# EtnaNode1_0.net
KiCad netlist of a schematic drawn in EAGLE
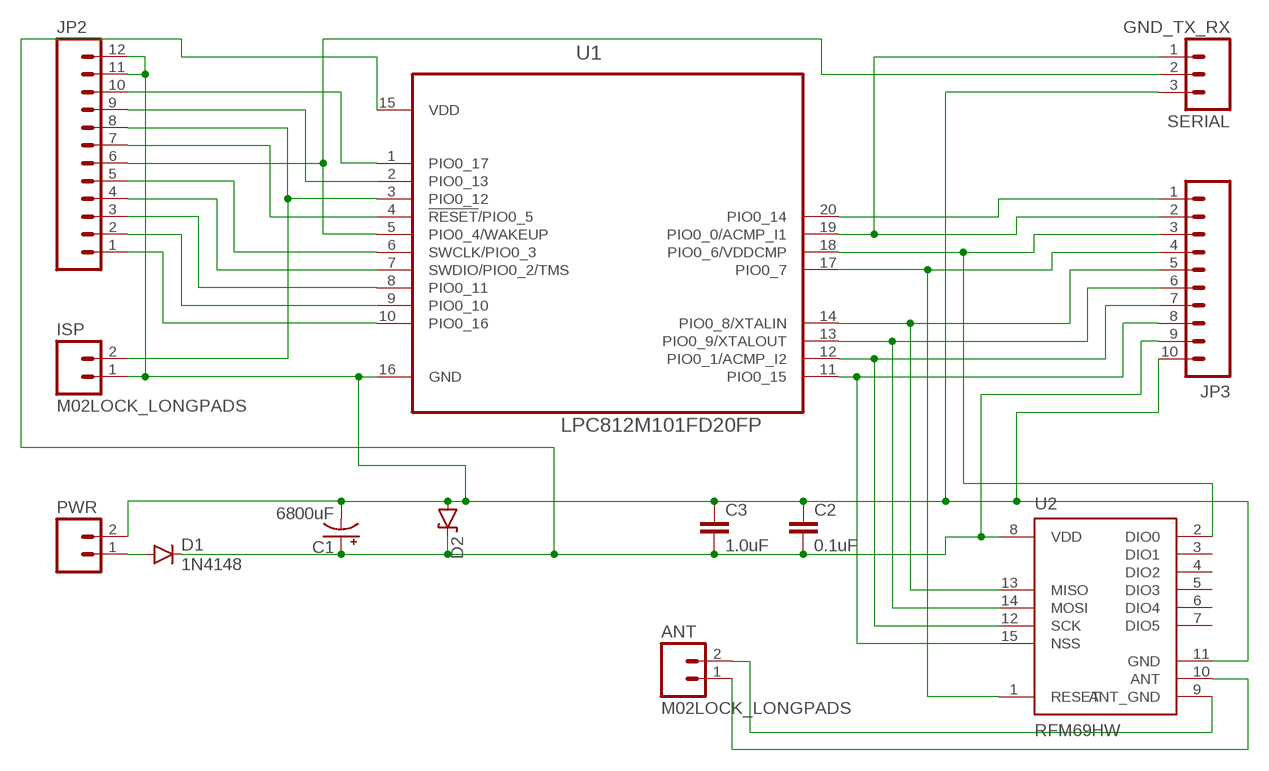
[diagram p0: schematic, sheet 1]

(export (version "E")
  (design (tool "Eeschema 10.0.6"))
  (components
    (comp (ref "ANT")
      (value "M02LOCK_LONGPADS")
      (footprint "eagle-import:1X02_LOCK_LONGPADS")
      (libsource (lib "eagle-import") (part "M02LOCK_LONGPADS"))
    )
    (comp (ref "C1")
      (value "6800uF")
      (footprint "eagle-import:CPOL-RADIAL-1000UF-25V")
      (libsource (lib "eagle-import") (part "CAP_POLPTH4"))
    )
    (comp (ref "C2")
      (value "0.1uF")
      (footprint "eagle-import:CAP-PTH-SMALL")
      (libsource (lib "eagle-import") (part "CAPPTH"))
    )
    (comp (ref "C3")
      (value "1.0uF")
      (footprint "eagle-import:CAP-PTH-SMALL")
      (libsource (lib "eagle-import") (part "CAPPTH"))
    )
    (comp (ref "D1")
      (value "1N4148")
      (footprint "eagle-import:DIODE-1N4148")
      (libsource (lib "eagle-import") (part "DIODE1N4148"))
    )
    (comp (ref "D2")
      (value "DIODE-ZENERPTH")
      (footprint "eagle-import:DIODE-ZENER")
      (libsource (lib "eagle-import") (part "DIODE-ZENERPTH"))
    )
    (comp (ref "ISP")
      (value "M02LOCK_LONGPADS")
      (footprint "eagle-import:1X02_LOCK_LONGPADS")
      (libsource (lib "eagle-import") (part "M02LOCK_LONGPADS"))
    )
    (comp (ref "JP2")
      (value "M12LOCK_LONGPADS")
      (footprint "eagle-import:1X12_LOCK_LONGPADS")
      (libsource (lib "eagle-import") (part "M12LOCK_LONGPADS"))
    )
    (comp (ref "JP3")
      (value "M10LOCK_LONGPADS")
      (footprint "eagle-import:1X10_LOCK_LONGPADS")
      (libsource (lib "eagle-import") (part "M10LOCK_LONGPADS"))
    )
    (comp (ref "PWR")
      (value "M02LOCK_LONGPADS")
      (footprint "eagle-import:1X02_LOCK_LONGPADS")
      (libsource (lib "eagle-import") (part "M02LOCK_LONGPADS"))
    )
    (comp (ref "SERIAL")
      (value "GND_TX_RX")
      (footprint "eagle-import:1X03_LOCK_LONGPADS")
      (libsource (lib "eagle-import") (part "M03LOCK_LONGPADS"))
    )
    (comp (ref "U1")
      (value "LPC812M101FD20FP")
      (footprint "eagle-import:SOIC127P1032X265-20N")
      (libsource (lib "eagle-import") (part "LPC812M101FD20FP"))
    )
    (comp (ref "U2")
      (value "RFM69HW")
      (footprint "eagle-import:RFM69W-XXXS2")
      (libsource (lib "eagle-import") (part "RFM69HW"))
    )
  )
  (nets
    (net (code "1") (name "Net-(D1-PadA)") (class "Default")
      (node (ref "D1") (pin "A") (pinfunction "A_A") (pintype "passive"))
      (node (ref "PWR") (pin "1") (pinfunction "1_1") (pintype "passive"))
    )
    (net (code "2") (name "Net-(D2-A)") (class "Default")
      (node (ref "C1") (pin "-") (pinfunction "-_-") (pintype "passive"))
      (node (ref "C2") (pin "1") (pinfunction "1_1") (pintype "passive"))
      (node (ref "C3") (pin "1") (pinfunction "1_1") (pintype "passive"))
      (node (ref "D2") (pin "P$2") (pinfunction "A_P$2") (pintype "passive"))
      (node (ref "ISP") (pin "1") (pinfunction "1_1") (pintype "passive"))
      (node (ref "JP2") (pin "11") (pinfunction "11_11") (pintype "passive"))
      (node (ref "JP2") (pin "12") (pinfunction "VCC_12") (pintype "passive"))
      (node (ref "JP3") (pin "10") (pinfunction "10_10") (pintype "passive"))
      (node (ref "PWR") (pin "2") (pinfunction "2_2") (pintype "passive"))
      (node (ref "SERIAL") (pin "3") (pinfunction "U0_RXD_3") (pintype "passive"))
      (node (ref "U1") (pin "16") (pinfunction "GND_16") (pintype "power_in"))
      (node (ref "U2") (pin "11") (pinfunction "GND_11") (pintype "power_in"))
    )
    (net (code "3") (name "Net-(D2-C)") (class "Default")
      (node (ref "C1") (pin "+") (pinfunction "+_+") (pintype "passive"))
      (node (ref "C2") (pin "2") (pinfunction "2_2") (pintype "passive"))
      (node (ref "C3") (pin "2") (pinfunction "2_2") (pintype "passive"))
      (node (ref "D1") (pin "C") (pinfunction "C_C") (pintype "passive"))
      (node (ref "D2") (pin "P$1") (pinfunction "C_P$1") (pintype "passive"))
      (node (ref "JP3") (pin "9") (pinfunction "9_9") (pintype "passive"))
      (node (ref "U1") (pin "15") (pinfunction "VDD_15") (pintype "power_in"))
      (node (ref "U2") (pin "8") (pinfunction "VDD_8") (pintype "power_in"))
    )
    (net (code "4") (name "Net-(SERIAL-GND)") (class "Default")
      (node (ref "JP3") (pin "2") (pinfunction "2_2") (pintype "passive"))
      (node (ref "SERIAL") (pin "1") (pinfunction "GND_1") (pintype "passive"))
      (node (ref "U1") (pin "19") (pinfunction "PIO0_0/ACMP_I1_19") (pintype "bidirectional"))
    )
    (net (code "5") (name "Net-(SERIAL-U0_TXD)") (class "Default")
      (node (ref "JP2") (pin "6") (pinfunction "6_6") (pintype "passive"))
      (node (ref "SERIAL") (pin "2") (pinfunction "U0_TXD_2") (pintype "passive"))
      (node (ref "U1") (pin "5") (pinfunction "PIO0_4/WAKEUP_5") (pintype "bidirectional"))
    )
    (net (code "6") (name "Net-(U1-PIO0_1{slash}ACMP_I2)") (class "Default")
      (node (ref "JP3") (pin "7") (pinfunction "7_7") (pintype "passive"))
      (node (ref "U1") (pin "12") (pinfunction "PIO0_1/ACMP_I2_12") (pintype "bidirectional"))
      (node (ref "U2") (pin "12") (pinfunction "SCK_12") (pintype "input"))
    )
    (net (code "7") (name "Net-(U1-PIO0_6{slash}VDDCMP)") (class "Default")
      (node (ref "JP3") (pin "3") (pinfunction "3_3") (pintype "passive"))
      (node (ref "U1") (pin "18") (pinfunction "PIO0_6/VDDCMP_18") (pintype "bidirectional"))
      (node (ref "U2") (pin "2") (pinfunction "DIO0_2") (pintype "bidirectional"))
    )
    (net (code "8") (name "Net-(U1-PIO0_7)") (class "Default")
      (node (ref "JP3") (pin "4") (pinfunction "4_4") (pintype "passive"))
      (node (ref "U1") (pin "17") (pinfunction "PIO0_7_17") (pintype "bidirectional"))
      (node (ref "U2") (pin "1") (pinfunction "RESET_1") (pintype "input"))
    )
    (net (code "9") (name "Net-(U1-PIO0_8{slash}XTALIN)") (class "Default")
      (node (ref "JP3") (pin "5") (pinfunction "5_5") (pintype "passive"))
      (node (ref "U1") (pin "14") (pinfunction "PIO0_8/XTALIN_14") (pintype "bidirectional"))
      (node (ref "U2") (pin "13") (pinfunction "MISO_13") (pintype "bidirectional"))
    )
    (net (code "10") (name "Net-(U1-PIO0_9{slash}XTALOUT)") (class "Default")
      (node (ref "JP3") (pin "6") (pinfunction "6_6") (pintype "passive"))
      (node (ref "U1") (pin "13") (pinfunction "PIO0_9/XTALOUT_13") (pintype "bidirectional"))
      (node (ref "U2") (pin "14") (pinfunction "MOSI_14") (pintype "input"))
    )
    (net (code "11") (name "Net-(U1-PIO0_10)") (class "Default")
      (node (ref "JP2") (pin "2") (pinfunction "2_2") (pintype "passive"))
      (node (ref "U1") (pin "9") (pinfunction "PIO0_10_9") (pintype "input"))
    )
    (net (code "12") (name "Net-(U1-PIO0_11)") (class "Default")
      (node (ref "JP2") (pin "3") (pinfunction "3_3") (pintype "passive"))
      (node (ref "U1") (pin "8") (pinfunction "PIO0_11_8") (pintype "input"))
    )
    (net (code "13") (name "Net-(U1-PIO0_12)") (class "Default")
      (node (ref "ISP") (pin "2") (pinfunction "2_2") (pintype "passive"))
      (node (ref "JP2") (pin "8") (pinfunction "8_8") (pintype "passive"))
      (node (ref "U1") (pin "3") (pinfunction "PIO0_12_3") (pintype "bidirectional"))
    )
    (net (code "14") (name "Net-(U1-PIO0_13)") (class "Default")
      (node (ref "JP2") (pin "9") (pinfunction "9_9") (pintype "passive"))
      (node (ref "U1") (pin "2") (pinfunction "PIO0_13_2") (pintype "bidirectional"))
    )
    (net (code "15") (name "Net-(U1-PIO0_14)") (class "Default")
      (node (ref "JP3") (pin "1") (pinfunction "1_1") (pintype "passive"))
      (node (ref "U1") (pin "20") (pinfunction "PIO0_14_20") (pintype "bidirectional"))
    )
    (net (code "16") (name "Net-(U1-PIO0_15)") (class "Default")
      (node (ref "JP3") (pin "8") (pinfunction "8_8") (pintype "passive"))
      (node (ref "U1") (pin "11") (pinfunction "PIO0_15_11") (pintype "bidirectional"))
      (node (ref "U2") (pin "15") (pinfunction "NSS_15") (pintype "input"))
    )
    (net (code "17") (name "Net-(U1-PIO0_16)") (class "Default")
      (node (ref "JP2") (pin "1") (pinfunction "1_1") (pintype "passive"))
      (node (ref "U1") (pin "10") (pinfunction "PIO0_16_10") (pintype "bidirectional"))
    )
    (net (code "18") (name "Net-(U1-PIO0_17)") (class "Default")
      (node (ref "JP2") (pin "10") (pinfunction "10_10") (pintype "passive"))
      (node (ref "U1") (pin "1") (pinfunction "PIO0_17_1") (pintype "bidirectional"))
    )
    (net (code "19") (name "Net-(U1-SWCLK{slash}PIO0_3)") (class "Default")
      (node (ref "JP2") (pin "5") (pinfunction "5_5") (pintype "passive"))
      (node (ref "U1") (pin "6") (pinfunction "SWCLK/PIO0_3_6") (pintype "bidirectional"))
    )
    (net (code "20") (name "Net-(U1-SWDIO{slash}PIO0_2{slash}TMS)") (class "Default")
      (node (ref "JP2") (pin "4") (pinfunction "4_4") (pintype "passive"))
      (node (ref "U1") (pin "7") (pinfunction "SWDIO/PIO0_2/TMS_7") (pintype "bidirectional"))
    )
    (net (code "21") (name "Net-(U1-~{RESET}{slash}PIO0_5)") (class "Default")
      (node (ref "JP2") (pin "7") (pinfunction "7_7") (pintype "passive"))
      (node (ref "U1") (pin "4") (pinfunction "~{RESET}/PIO0_5_4") (pintype "bidirectional"))
    )
    (net (code "22") (name "Net-(U2-ANT)") (class "Default")
      (node (ref "ANT") (pin "1") (pinfunction "1_1") (pintype "passive"))
      (node (ref "U2") (pin "10") (pinfunction "ANT_10") (pintype "passive"))
    )
    (net (code "23") (name "Net-(U2-ANT_GND)") (class "Default")
      (node (ref "ANT") (pin "2") (pinfunction "2_2") (pintype "passive"))
      (node (ref "U2") (pin "9") (pinfunction "ANT_GND_9") (pintype "power_in"))
    )
    (net (code "24") (name "unconnected-(U2-DIO1-Pad3)") (class "Default")
      (node (ref "U2") (pin "3") (pinfunction "DIO1_3") (pintype "bidirectional"))
    )
    (net (code "25") (name "unconnected-(U2-DIO2-Pad4)") (class "Default")
      (node (ref "U2") (pin "4") (pinfunction "DIO2_4") (pintype "bidirectional"))
    )
    (net (code "26") (name "unconnected-(U2-DIO3-Pad5)") (class "Default")
      (node (ref "U2") (pin "5") (pinfunction "DIO3_5") (pintype "bidirectional"))
    )
    (net (code "27") (name "unconnected-(U2-DIO4-Pad6)") (class "Default")
      (node (ref "U2") (pin "6") (pinfunction "DIO4_6") (pintype "bidirectional"))
    )
    (net (code "28") (name "unconnected-(U2-DIO5-Pad7)") (class "Default")
      (node (ref "U2") (pin "7") (pinfunction "DIO5_7") (pintype "bidirectional"))
    )
  )
)
